# rcstick-f.net
KiCad netlist of a schematic drawn in EAGLE
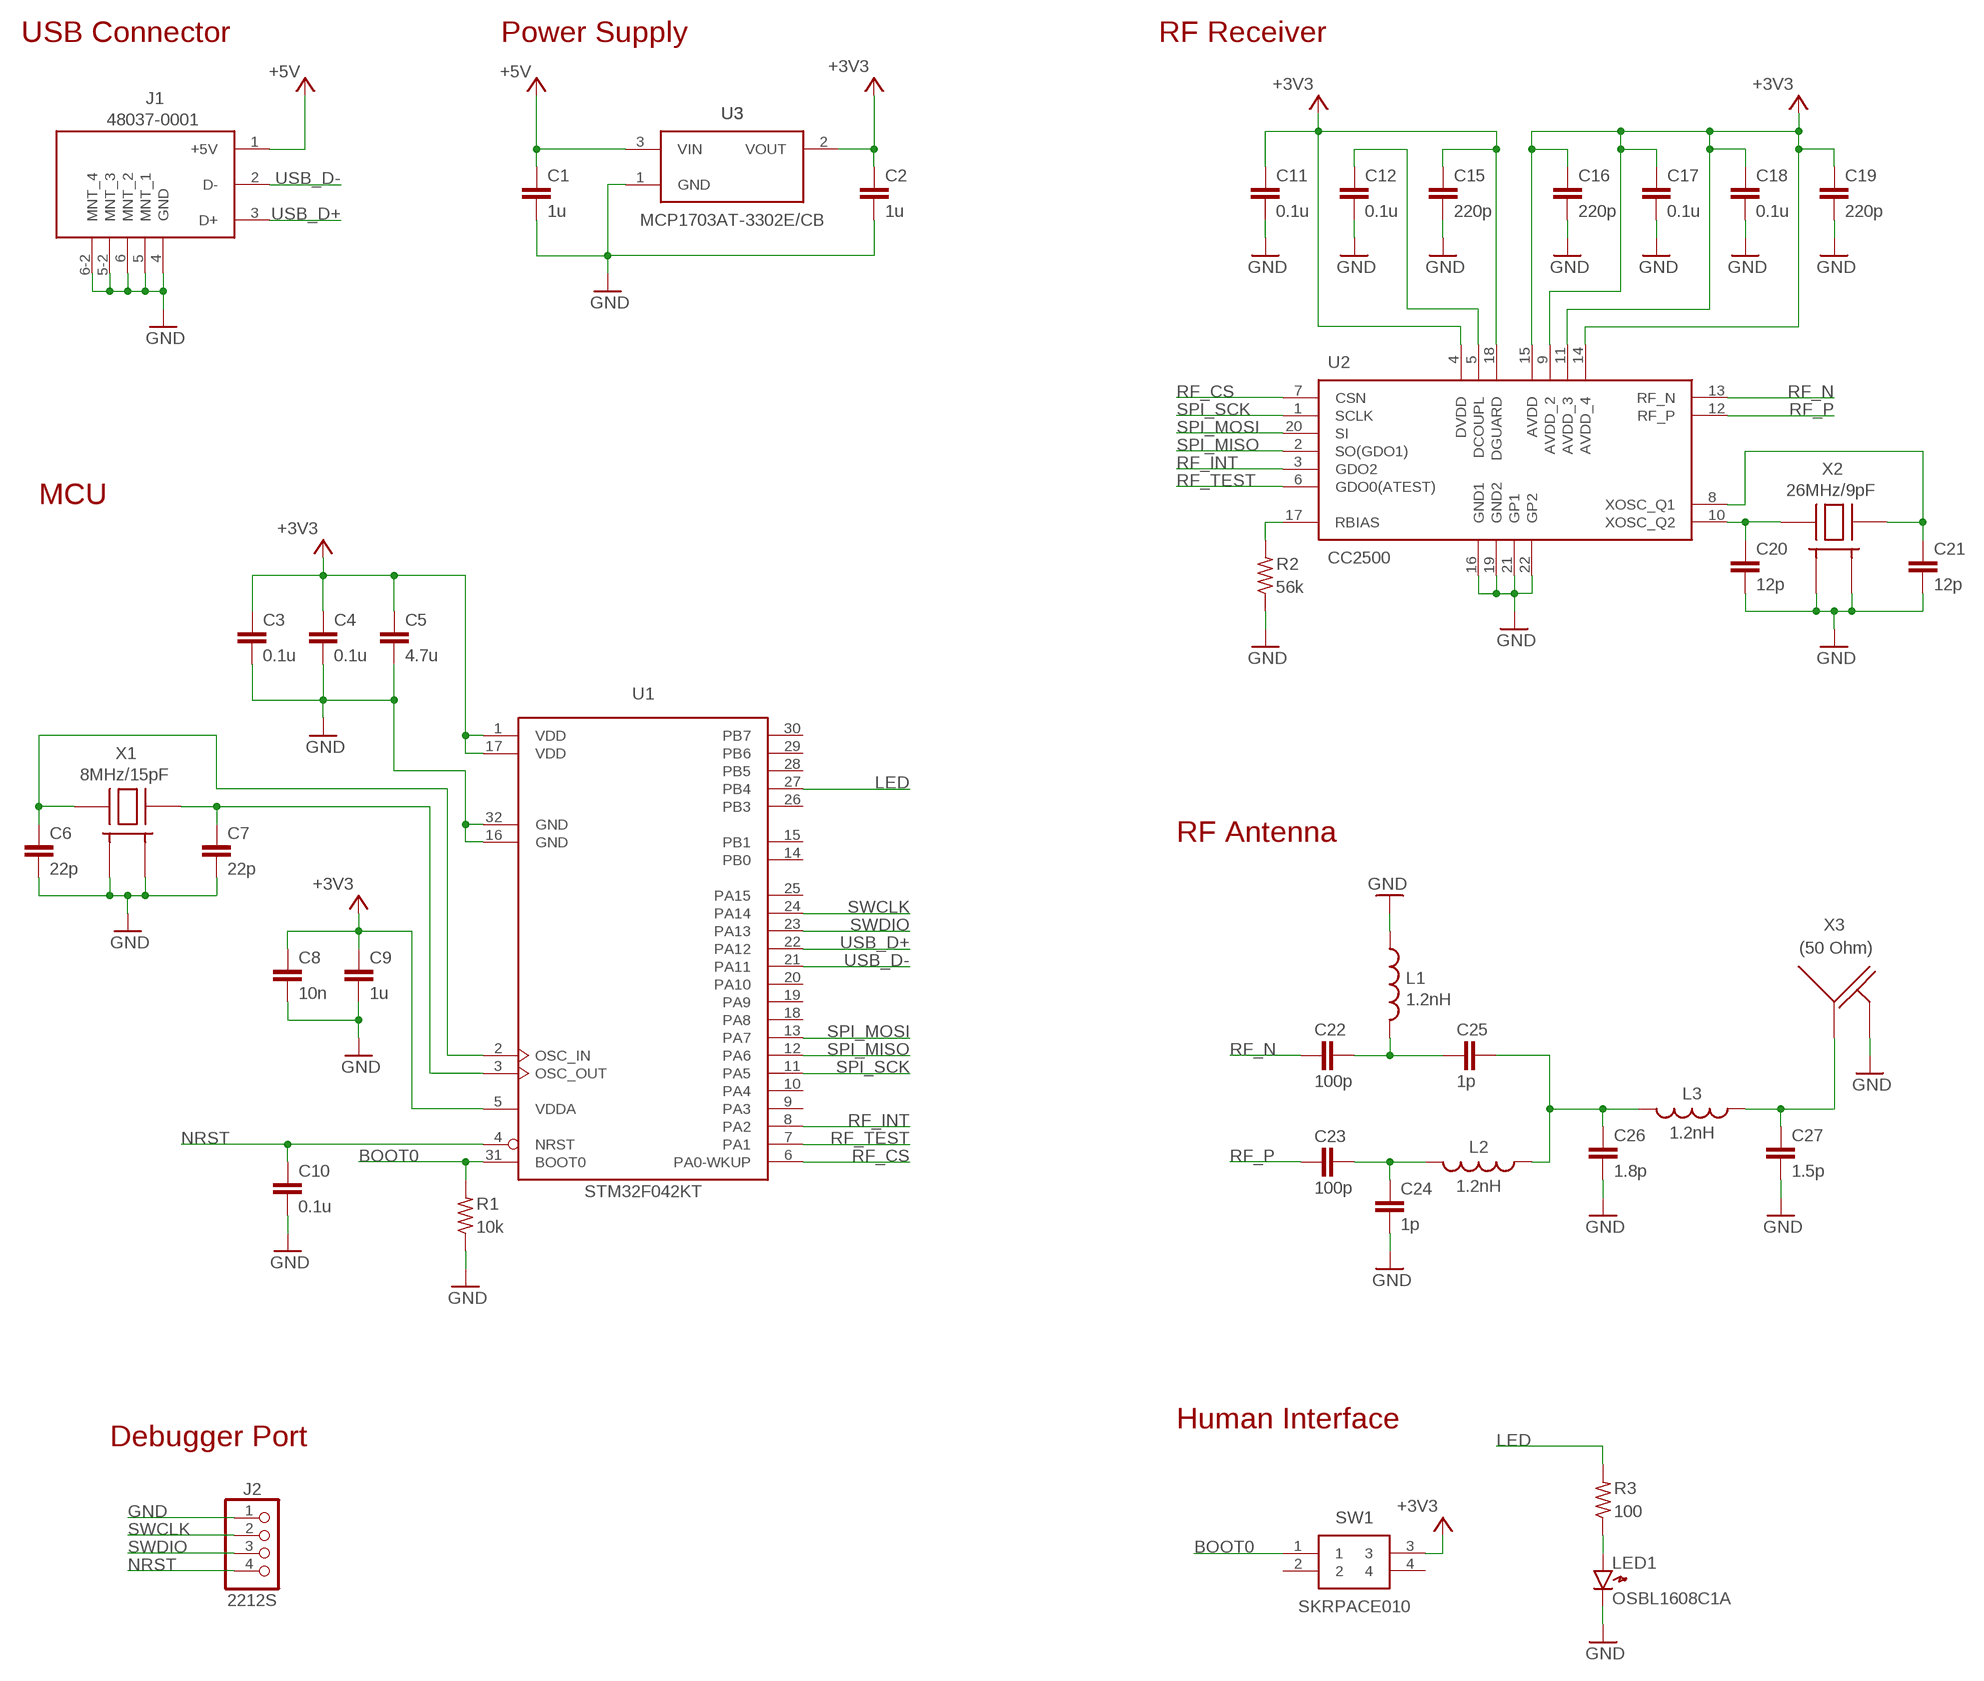
[diagram p0: schematic, sheet 1]

(export (version "E")
  (design (tool "Eeschema 10.0.6"))
  (components
    (comp (ref "C1")
      (value "1u")
      (footprint "eagle-import:RCL_C0402_HS")
      (libsource (lib "eagle-import") (part "RCL_C-EUC0402-HS"))
    )
    (comp (ref "C2")
      (value "1u")
      (footprint "eagle-import:RCL_C0402_HS")
      (libsource (lib "eagle-import") (part "RCL_C-EUC0402-HS"))
    )
    (comp (ref "C3")
      (value "0.1u")
      (footprint "eagle-import:RCL_C0402_HS")
      (libsource (lib "eagle-import") (part "RCL_C-EUC0402-HS"))
    )
    (comp (ref "C4")
      (value "0.1u")
      (footprint "eagle-import:RCL_C0402_HS")
      (libsource (lib "eagle-import") (part "RCL_C-EUC0402-HS"))
    )
    (comp (ref "C5")
      (value "4.7u")
      (footprint "eagle-import:RCL_C0402_HS")
      (libsource (lib "eagle-import") (part "RCL_C-EUC0402-HS"))
    )
    (comp (ref "C6")
      (value "22p")
      (footprint "eagle-import:RCL_C0402_HS")
      (libsource (lib "eagle-import") (part "RCL_C-EUC0402-HS"))
    )
    (comp (ref "C7")
      (value "22p")
      (footprint "eagle-import:RCL_C0402_HS")
      (libsource (lib "eagle-import") (part "RCL_C-EUC0402-HS"))
    )
    (comp (ref "C8")
      (value "10n")
      (footprint "eagle-import:RCL_C0402_HS")
      (libsource (lib "eagle-import") (part "RCL_C-EUC0402-HS"))
    )
    (comp (ref "C9")
      (value "1u")
      (footprint "eagle-import:RCL_C0402_HS")
      (libsource (lib "eagle-import") (part "RCL_C-EUC0402-HS"))
    )
    (comp (ref "C10")
      (value "0.1u")
      (footprint "eagle-import:RCL_C0402_HS")
      (libsource (lib "eagle-import") (part "RCL_C-EUC0402-HS"))
    )
    (comp (ref "C11")
      (value "0.1u")
      (footprint "eagle-import:RCL_C0402_HS")
      (libsource (lib "eagle-import") (part "RCL_C-EUC0402-HS"))
    )
    (comp (ref "C12")
      (value "0.1u")
      (footprint "eagle-import:RCL_C0402_HS")
      (libsource (lib "eagle-import") (part "RCL_C-EUC0402-HS"))
    )
    (comp (ref "C15")
      (value "220p")
      (footprint "eagle-import:RCL_C0402_HS")
      (libsource (lib "eagle-import") (part "RCL_C-EUC0402-HS"))
    )
    (comp (ref "C16")
      (value "220p")
      (footprint "eagle-import:RCL_C0402_HS")
      (libsource (lib "eagle-import") (part "RCL_C-EUC0402-HS"))
    )
    (comp (ref "C17")
      (value "0.1u")
      (footprint "eagle-import:RCL_C0402_HS")
      (libsource (lib "eagle-import") (part "RCL_C-EUC0402-HS"))
    )
    (comp (ref "C18")
      (value "0.1u")
      (footprint "eagle-import:RCL_C0402_HS")
      (libsource (lib "eagle-import") (part "RCL_C-EUC0402-HS"))
    )
    (comp (ref "C19")
      (value "220p")
      (footprint "eagle-import:RCL_C0402_HS")
      (libsource (lib "eagle-import") (part "RCL_C-EUC0402-HS"))
    )
    (comp (ref "C20")
      (value "12p")
      (footprint "eagle-import:RCL_C0402_HS")
      (libsource (lib "eagle-import") (part "RCL_C-EUC0402-HS"))
    )
    (comp (ref "C21")
      (value "12p")
      (footprint "eagle-import:RCL_C0402_HS")
      (libsource (lib "eagle-import") (part "RCL_C-EUC0402-HS"))
    )
    (comp (ref "C22")
      (value "100p")
      (footprint "eagle-import:RCL_C0402_HS")
      (libsource (lib "eagle-import") (part "RCL_C-EUC0402-HS"))
    )
    (comp (ref "C23")
      (value "100p")
      (footprint "eagle-import:RCL_C0402_HS")
      (libsource (lib "eagle-import") (part "RCL_C-EUC0402-HS"))
    )
    (comp (ref "C24")
      (value "1p")
      (footprint "eagle-import:RCL_C0402_HS")
      (libsource (lib "eagle-import") (part "RCL_C-EUC0402-HS"))
    )
    (comp (ref "C25")
      (value "1p")
      (footprint "eagle-import:RCL_C0402_HS")
      (libsource (lib "eagle-import") (part "RCL_C-EUC0402-HS"))
    )
    (comp (ref "C26")
      (value "1.8p")
      (footprint "eagle-import:RCL_C0402_HS")
      (libsource (lib "eagle-import") (part "RCL_C-EUC0402-HS"))
    )
    (comp (ref "C27")
      (value "1.5p")
      (footprint "eagle-import:RCL_C0402_HS")
      (libsource (lib "eagle-import") (part "RCL_C-EUC0402-HS"))
    )
    (comp (ref "J1")
      (value "MOLEX_48037-0001")
      (footprint "eagle-import:MOLEX_48037-0001_1")
      (libsource (lib "eagle-import") (part "MOLEX_48037-0001"))
    )
    (comp (ref "J2")
      (value "2212S")
      (footprint "eagle-import:CONNECTOR_STD-1X4")
      (libsource (lib "eagle-import") (part "CONNECTOR_STD-PINHD-1X4"))
    )
    (comp (ref "L1")
      (value "1.2nH")
      (footprint "eagle-import:RCL_L0402_HS")
      (libsource (lib "eagle-import") (part "RCL_L-USL0402-HS"))
    )
    (comp (ref "L2")
      (value "1.2nH")
      (footprint "eagle-import:RCL_L0402_HS")
      (libsource (lib "eagle-import") (part "RCL_L-USL0402-HS"))
    )
    (comp (ref "L3")
      (value "1.2nH")
      (footprint "eagle-import:RCL_L0402_HS")
      (libsource (lib "eagle-import") (part "RCL_L-USL0402-HS"))
    )
    (comp (ref "LED1")
      (value "OSBL1608C1A")
      (footprint "eagle-import:LED1608")
      (libsource (lib "eagle-import") (part "LED1608"))
    )
    (comp (ref "R1")
      (value "10k")
      (footprint "eagle-import:RCL_R0402_HS")
      (libsource (lib "eagle-import") (part "RCL_R-US_R0402-HS"))
    )
    (comp (ref "R2")
      (value "56k")
      (footprint "eagle-import:RCL_R0402_HS")
      (libsource (lib "eagle-import") (part "RCL_R-US_R0402-HS"))
    )
    (comp (ref "R3")
      (value "100")
      (footprint "eagle-import:RCL_R0402_HS")
      (libsource (lib "eagle-import") (part "RCL_R-US_R0402-HS"))
    )
    (comp (ref "SW1")
      (value "SKRPACE010")
      (footprint "eagle-import:SMT(4.2X3.2)")
      (libsource (lib "eagle-import") (part "SKRPACE010"))
    )
    (comp (ref "U1")
      (value "STM32F042KT")
      (footprint "eagle-import:LQFP32-M")
      (libsource (lib "eagle-import") (part "STM32F042KT"))
    )
    (comp (ref "U2")
      (value "CC2500")
      (footprint "eagle-import:CC2500-RTY1_CC2500-HS")
      (libsource (lib "eagle-import") (part "CC2500-HS"))
    )
    (comp (ref "U3")
      (value "MCP1703AT-3302E/CB")
      (footprint "eagle-import:SOT23")
      (libsource (lib "eagle-import") (part "LDO-REGULATOR"))
    )
    (comp (ref "X1")
      (value "8MHz/15pF")
      (footprint "eagle-import:CRYSTAL3225-HS")
      (libsource (lib "eagle-import") (part "CRYSTAL3225HS"))
    )
    (comp (ref "X2")
      (value "26MHz/9pF")
      (footprint "eagle-import:CRYSTAL3225-HS")
      (libsource (lib "eagle-import") (part "CRYSTAL3225HS"))
    )
    (comp (ref "X3")
      (value "(50 Ohm)")
      (footprint "eagle-import:2.4GHZ-INVERTED-F-LARGE-FLIP")
      (libsource (lib "eagle-import") (part "2.4GHZ-INVERED-FLARGE-FLIP"))
    )
  )
  (nets
    (net (code "1") (name "+3V3") (class "Default")
      (node (ref "C11") (pin "1") (pinfunction "1_1") (pintype "passive"))
      (node (ref "C15") (pin "1") (pinfunction "1_1") (pintype "passive"))
      (node (ref "C16") (pin "1") (pinfunction "1_1") (pintype "passive"))
      (node (ref "C17") (pin "1") (pinfunction "1_1") (pintype "passive"))
      (node (ref "C18") (pin "1") (pinfunction "1_1") (pintype "passive"))
      (node (ref "C19") (pin "1") (pinfunction "1_1") (pintype "passive"))
      (node (ref "C2") (pin "1") (pinfunction "1_1") (pintype "passive"))
      (node (ref "C3") (pin "1") (pinfunction "1_1") (pintype "passive"))
      (node (ref "C4") (pin "1") (pinfunction "1_1") (pintype "passive"))
      (node (ref "C5") (pin "1") (pinfunction "1_1") (pintype "passive"))
      (node (ref "C8") (pin "1") (pinfunction "1_1") (pintype "passive"))
      (node (ref "C9") (pin "1") (pinfunction "1_1") (pintype "passive"))
      (node (ref "SW1") (pin "3") (pinfunction "3_3") (pintype "bidirectional"))
      (node (ref "U1") (pin "1") (pinfunction "VDD_1") (pintype "power_in"))
      (node (ref "U1") (pin "17") (pinfunction "VDD_17") (pintype "power_in"))
      (node (ref "U1") (pin "5") (pinfunction "VDDA_5") (pintype "power_in"))
      (node (ref "U2") (pin "11") (pinfunction "AVDD_3_11") (pintype "bidirectional"))
      (node (ref "U2") (pin "14") (pinfunction "AVDD_4_14") (pintype "bidirectional"))
      (node (ref "U2") (pin "15") (pinfunction "AVDD_15") (pintype "bidirectional"))
      (node (ref "U2") (pin "18") (pinfunction "DGUARD_18") (pintype "bidirectional"))
      (node (ref "U2") (pin "4") (pinfunction "DVDD_4") (pintype "bidirectional"))
      (node (ref "U2") (pin "9") (pinfunction "AVDD_2_9") (pintype "bidirectional"))
      (node (ref "U3") (pin "2") (pinfunction "VOUT_2") (pintype "bidirectional"))
    )
    (net (code "2") (name "+5V") (class "Default")
      (node (ref "C1") (pin "1") (pinfunction "1_1") (pintype "passive"))
      (node (ref "J1") (pin "1") (pinfunction "+5V_1") (pintype "bidirectional"))
      (node (ref "U3") (pin "3") (pinfunction "VIN_3") (pintype "bidirectional"))
    )
    (net (code "3") (name "/BOOT0") (class "Default")
      (node (ref "R1") (pin "2") (pinfunction "2_2") (pintype "passive"))
      (node (ref "SW1") (pin "1") (pinfunction "1_1") (pintype "bidirectional"))
      (node (ref "U1") (pin "31") (pinfunction "BOOT0_31") (pintype "input"))
    )
    (net (code "4") (name "/LED") (class "Default")
      (node (ref "R3") (pin "2") (pinfunction "2_2") (pintype "passive"))
      (node (ref "U1") (pin "27") (pinfunction "PB4_27") (pintype "bidirectional"))
    )
    (net (code "5") (name "/NRST") (class "Default")
      (node (ref "C10") (pin "1") (pinfunction "1_1") (pintype "passive"))
      (node (ref "J2") (pin "4") (pinfunction "4_4") (pintype "passive"))
      (node (ref "U1") (pin "4") (pinfunction "NRST_4") (pintype "bidirectional"))
    )
    (net (code "6") (name "/RF_CS") (class "Default")
      (node (ref "U1") (pin "6") (pinfunction "PA0-WKUP_6") (pintype "bidirectional"))
      (node (ref "U2") (pin "7") (pinfunction "CSN_7") (pintype "bidirectional"))
    )
    (net (code "7") (name "/RF_INT") (class "Default")
      (node (ref "U1") (pin "8") (pinfunction "PA2_8") (pintype "bidirectional"))
      (node (ref "U2") (pin "3") (pinfunction "GDO2_3") (pintype "bidirectional"))
    )
    (net (code "8") (name "/RF_N") (class "Default")
      (node (ref "C22") (pin "1") (pinfunction "1_1") (pintype "passive"))
      (node (ref "U2") (pin "13") (pinfunction "RF_N_13") (pintype "bidirectional"))
    )
    (net (code "9") (name "/RF_P") (class "Default")
      (node (ref "C23") (pin "1") (pinfunction "1_1") (pintype "passive"))
      (node (ref "U2") (pin "12") (pinfunction "RF_P_12") (pintype "bidirectional"))
    )
    (net (code "10") (name "/RF_TEST") (class "Default")
      (node (ref "U1") (pin "7") (pinfunction "PA1_7") (pintype "bidirectional"))
      (node (ref "U2") (pin "6") (pinfunction "GDO0(ATEST)_6") (pintype "bidirectional"))
    )
    (net (code "11") (name "/SPI_MISO") (class "Default")
      (node (ref "U1") (pin "12") (pinfunction "PA6_12") (pintype "bidirectional"))
      (node (ref "U2") (pin "2") (pinfunction "SO(GDO1)_2") (pintype "bidirectional"))
    )
    (net (code "12") (name "/SPI_MOSI") (class "Default")
      (node (ref "U1") (pin "13") (pinfunction "PA7_13") (pintype "bidirectional"))
      (node (ref "U2") (pin "20") (pinfunction "SI_20") (pintype "bidirectional"))
    )
    (net (code "13") (name "/SPI_SCK") (class "Default")
      (node (ref "U1") (pin "11") (pinfunction "PA5_11") (pintype "bidirectional"))
      (node (ref "U2") (pin "1") (pinfunction "SCLK_1") (pintype "bidirectional"))
    )
    (net (code "14") (name "/SWCLK") (class "Default")
      (node (ref "J2") (pin "2") (pinfunction "2_2") (pintype "passive"))
      (node (ref "U1") (pin "24") (pinfunction "PA14_24") (pintype "bidirectional"))
    )
    (net (code "15") (name "/SWDIO") (class "Default")
      (node (ref "J2") (pin "3") (pinfunction "3_3") (pintype "passive"))
      (node (ref "U1") (pin "23") (pinfunction "PA13_23") (pintype "bidirectional"))
    )
    (net (code "16") (name "/USB_D+") (class "Default")
      (node (ref "J1") (pin "3") (pinfunction "D+_3") (pintype "bidirectional"))
      (node (ref "U1") (pin "22") (pinfunction "PA12_22") (pintype "bidirectional"))
    )
    (net (code "17") (name "/USB_D-") (class "Default")
      (node (ref "J1") (pin "2") (pinfunction "D-_2") (pintype "bidirectional"))
      (node (ref "U1") (pin "21") (pinfunction "PA11_21") (pintype "bidirectional"))
    )
    (net (code "18") (name "GND") (class "Default")
      (node (ref "C1") (pin "2") (pinfunction "2_2") (pintype "passive"))
      (node (ref "C10") (pin "2") (pinfunction "2_2") (pintype "passive"))
      (node (ref "C11") (pin "2") (pinfunction "2_2") (pintype "passive"))
      (node (ref "C12") (pin "2") (pinfunction "2_2") (pintype "passive"))
      (node (ref "C15") (pin "2") (pinfunction "2_2") (pintype "passive"))
      (node (ref "C16") (pin "2") (pinfunction "2_2") (pintype "passive"))
      (node (ref "C17") (pin "2") (pinfunction "2_2") (pintype "passive"))
      (node (ref "C18") (pin "2") (pinfunction "2_2") (pintype "passive"))
      (node (ref "C19") (pin "2") (pinfunction "2_2") (pintype "passive"))
      (node (ref "C2") (pin "2") (pinfunction "2_2") (pintype "passive"))
      (node (ref "C20") (pin "2") (pinfunction "2_2") (pintype "passive"))
      (node (ref "C21") (pin "2") (pinfunction "2_2") (pintype "passive"))
      (node (ref "C24") (pin "2") (pinfunction "2_2") (pintype "passive"))
      (node (ref "C26") (pin "2") (pinfunction "2_2") (pintype "passive"))
      (node (ref "C27") (pin "2") (pinfunction "2_2") (pintype "passive"))
      (node (ref "C3") (pin "2") (pinfunction "2_2") (pintype "passive"))
      (node (ref "C4") (pin "2") (pinfunction "2_2") (pintype "passive"))
      (node (ref "C5") (pin "2") (pinfunction "2_2") (pintype "passive"))
      (node (ref "C6") (pin "2") (pinfunction "2_2") (pintype "passive"))
      (node (ref "C7") (pin "2") (pinfunction "2_2") (pintype "passive"))
      (node (ref "C8") (pin "2") (pinfunction "2_2") (pintype "passive"))
      (node (ref "C9") (pin "2") (pinfunction "2_2") (pintype "passive"))
      (node (ref "J1") (pin "4") (pinfunction "GND_4") (pintype "bidirectional"))
      (node (ref "J1") (pin "5") (pinfunction "MNT_1_5") (pintype "bidirectional"))
      (node (ref "J1") (pin "5-2") (pinfunction "MNT_3_5-2") (pintype "bidirectional"))
      (node (ref "J1") (pin "6") (pinfunction "MNT_2_6") (pintype "bidirectional"))
      (node (ref "J1") (pin "6-2") (pinfunction "MNT_4_6-2") (pintype "bidirectional"))
      (node (ref "J2") (pin "1") (pinfunction "1_1") (pintype "passive"))
      (node (ref "L1") (pin "1") (pinfunction "1_1") (pintype "passive"))
      (node (ref "LED1") (pin "K") (pinfunction "K_K") (pintype "passive"))
      (node (ref "R1") (pin "1") (pinfunction "1_1") (pintype "passive"))
      (node (ref "R2") (pin "1") (pinfunction "1_1") (pintype "passive"))
      (node (ref "U1") (pin "16") (pinfunction "GND_16") (pintype "power_in"))
      (node (ref "U1") (pin "32") (pinfunction "GND_32") (pintype "power_in"))
      (node (ref "U2") (pin "16") (pinfunction "GND1_16") (pintype "bidirectional"))
      (node (ref "U2") (pin "19") (pinfunction "GND2_19") (pintype "bidirectional"))
      (node (ref "U2") (pin "21") (pinfunction "GP1_21") (pintype "bidirectional"))
      (node (ref "U2") (pin "22") (pinfunction "GP2_22") (pintype "bidirectional"))
      (node (ref "U3") (pin "1") (pinfunction "GND_1") (pintype "bidirectional"))
      (node (ref "X1") (pin "2") (pinfunction "GND_1_2") (pintype "bidirectional"))
      (node (ref "X1") (pin "4") (pinfunction "GND_2_4") (pintype "bidirectional"))
      (node (ref "X2") (pin "2") (pinfunction "GND_1_2") (pintype "bidirectional"))
      (node (ref "X2") (pin "4") (pinfunction "GND_2_4") (pintype "bidirectional"))
      (node (ref "X3") (pin "2") (pinfunction "GND_2") (pintype "bidirectional"))
    )
    (net (code "19") (name "Net-(C22-Pad2)") (class "Default")
      (node (ref "C22") (pin "2") (pinfunction "2_2") (pintype "passive"))
      (node (ref "C25") (pin "1") (pinfunction "1_1") (pintype "passive"))
      (node (ref "L1") (pin "2") (pinfunction "2_2") (pintype "passive"))
    )
    (net (code "20") (name "Net-(C23-Pad2)") (class "Default")
      (node (ref "C23") (pin "2") (pinfunction "2_2") (pintype "passive"))
      (node (ref "C24") (pin "1") (pinfunction "1_1") (pintype "passive"))
      (node (ref "L2") (pin "2") (pinfunction "2_2") (pintype "passive"))
    )
    (net (code "21") (name "Net-(C25-Pad2)") (class "Default")
      (node (ref "C25") (pin "2") (pinfunction "2_2") (pintype "passive"))
      (node (ref "C26") (pin "1") (pinfunction "1_1") (pintype "passive"))
      (node (ref "L2") (pin "1") (pinfunction "1_1") (pintype "passive"))
      (node (ref "L3") (pin "2") (pinfunction "2_2") (pintype "passive"))
    )
    (net (code "22") (name "Net-(LED1-PadA)") (class "Default")
      (node (ref "LED1") (pin "A") (pinfunction "A_A") (pintype "passive"))
      (node (ref "R3") (pin "1") (pinfunction "1_1") (pintype "passive"))
    )
    (net (code "23") (name "Net-(U1-OSC_IN)") (class "Default")
      (node (ref "C6") (pin "1") (pinfunction "1_1") (pintype "passive"))
      (node (ref "U1") (pin "2") (pinfunction "OSC_IN_2") (pintype "bidirectional"))
      (node (ref "X1") (pin "1") (pinfunction "HOT_1_1") (pintype "bidirectional"))
    )
    (net (code "24") (name "Net-(U1-OSC_OUT)") (class "Default")
      (node (ref "C7") (pin "1") (pinfunction "1_1") (pintype "passive"))
      (node (ref "U1") (pin "3") (pinfunction "OSC_OUT_3") (pintype "bidirectional"))
      (node (ref "X1") (pin "3") (pinfunction "HOT_2_3") (pintype "bidirectional"))
    )
    (net (code "25") (name "Net-(U2-DCOUPL)") (class "Default")
      (node (ref "C12") (pin "1") (pinfunction "1_1") (pintype "passive"))
      (node (ref "U2") (pin "5") (pinfunction "DCOUPL_5") (pintype "bidirectional"))
    )
    (net (code "26") (name "Net-(U2-RBIAS)") (class "Default")
      (node (ref "R2") (pin "2") (pinfunction "2_2") (pintype "passive"))
      (node (ref "U2") (pin "17") (pinfunction "RBIAS_17") (pintype "bidirectional"))
    )
    (net (code "27") (name "Net-(U2-XOSC_Q1)") (class "Default")
      (node (ref "C21") (pin "1") (pinfunction "1_1") (pintype "passive"))
      (node (ref "U2") (pin "8") (pinfunction "XOSC_Q1_8") (pintype "bidirectional"))
      (node (ref "X2") (pin "3") (pinfunction "HOT_2_3") (pintype "bidirectional"))
    )
    (net (code "28") (name "Net-(U2-XOSC_Q2)") (class "Default")
      (node (ref "C20") (pin "1") (pinfunction "1_1") (pintype "passive"))
      (node (ref "U2") (pin "10") (pinfunction "XOSC_Q2_10") (pintype "bidirectional"))
      (node (ref "X2") (pin "1") (pinfunction "HOT_1_1") (pintype "bidirectional"))
    )
    (net (code "29") (name "Net-(X3-ANT)") (class "Default")
      (node (ref "C27") (pin "1") (pinfunction "1_1") (pintype "passive"))
      (node (ref "L3") (pin "1") (pinfunction "1_1") (pintype "passive"))
      (node (ref "X3") (pin "1") (pinfunction "ANT_1") (pintype "bidirectional"))
    )
    (net (code "30") (name "unconnected-(SW1-Pad2)") (class "Default")
      (node (ref "SW1") (pin "2") (pinfunction "2_2") (pintype "bidirectional"))
    )
    (net (code "31") (name "unconnected-(SW1-Pad4)") (class "Default")
      (node (ref "SW1") (pin "4") (pinfunction "4_4") (pintype "bidirectional"))
    )
    (net (code "32") (name "unconnected-(U1-PA3-Pad9)") (class "Default")
      (node (ref "U1") (pin "9") (pinfunction "PA3_9") (pintype "bidirectional"))
    )
    (net (code "33") (name "unconnected-(U1-PA4-Pad10)") (class "Default")
      (node (ref "U1") (pin "10") (pinfunction "PA4_10") (pintype "bidirectional"))
    )
    (net (code "34") (name "unconnected-(U1-PA8-Pad18)") (class "Default")
      (node (ref "U1") (pin "18") (pinfunction "PA8_18") (pintype "bidirectional"))
    )
    (net (code "35") (name "unconnected-(U1-PA9-Pad19)") (class "Default")
      (node (ref "U1") (pin "19") (pinfunction "PA9_19") (pintype "bidirectional"))
    )
    (net (code "36") (name "unconnected-(U1-PA10-Pad20)") (class "Default")
      (node (ref "U1") (pin "20") (pinfunction "PA10_20") (pintype "bidirectional"))
    )
    (net (code "37") (name "unconnected-(U1-PA15-Pad25)") (class "Default")
      (node (ref "U1") (pin "25") (pinfunction "PA15_25") (pintype "bidirectional"))
    )
    (net (code "38") (name "unconnected-(U1-PB0-Pad14)") (class "Default")
      (node (ref "U1") (pin "14") (pinfunction "PB0_14") (pintype "bidirectional"))
    )
    (net (code "39") (name "unconnected-(U1-PB1-Pad15)") (class "Default")
      (node (ref "U1") (pin "15") (pinfunction "PB1_15") (pintype "bidirectional"))
    )
    (net (code "40") (name "unconnected-(U1-PB3-Pad26)") (class "Default")
      (node (ref "U1") (pin "26") (pinfunction "PB3_26") (pintype "bidirectional"))
    )
    (net (code "41") (name "unconnected-(U1-PB5-Pad28)") (class "Default")
      (node (ref "U1") (pin "28") (pinfunction "PB5_28") (pintype "bidirectional"))
    )
    (net (code "42") (name "unconnected-(U1-PB6-Pad29)") (class "Default")
      (node (ref "U1") (pin "29") (pinfunction "PB6_29") (pintype "bidirectional"))
    )
    (net (code "43") (name "unconnected-(U1-PB7-Pad30)") (class "Default")
      (node (ref "U1") (pin "30") (pinfunction "PB7_30") (pintype "bidirectional"))
    )
  )
)
